# Micro.net
KiCad netlist of a schematic drawn in Altium Designer
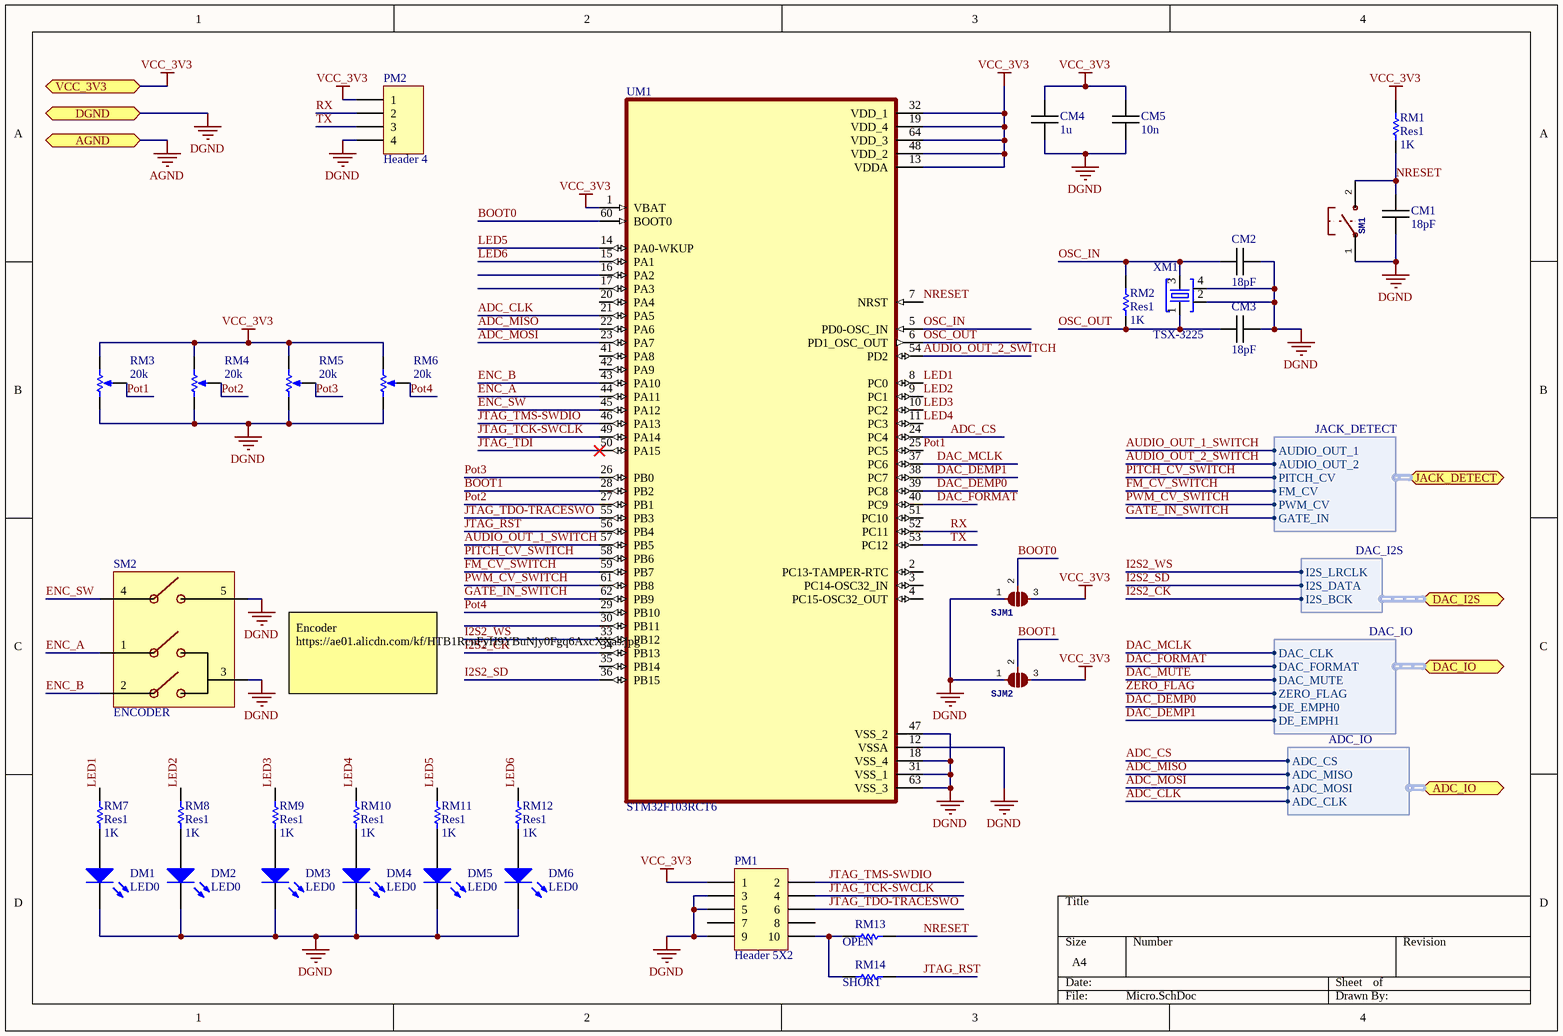
[diagram p0: Micro.SchDoc]

(export (version "E")
  (design (tool "Eeschema 10.0.6"))
  (components
    (comp (ref "CM1")
      (value "18pF")
      (footprint "C 0603 / 1608")
      (libsource (lib "Standard") (part "Capacitor"))
    )
    (comp (ref "CM2")
      (value "18pF")
      (footprint "C 0603 / 1608")
      (libsource (lib "Standard") (part "Capacitor"))
    )
    (comp (ref "CM3")
      (value "18pF")
      (footprint "C 0603 / 1608")
      (libsource (lib "Standard") (part "Capacitor"))
    )
    (comp (ref "CM4")
      (value "1u")
      (footprint "C 0603 / 1608")
      (libsource (lib "Standard") (part "Capacitor"))
    )
    (comp (ref "CM5")
      (value "10n")
      (footprint "C 0603 / 1608")
      (libsource (lib "Standard") (part "Capacitor"))
    )
    (comp (ref "DM1")
      (value "LED0")
      (footprint "LED2-2.54-D5.0MM")
      (description "Typical INFRARED GaAs LED")
      (fields (field (name "PUBLISHER") "Altium Limited"))
      (libsource (lib "Miscellaneous Devices") (part "LED0"))
    )
    (comp (ref "DM2")
      (value "LED0")
      (footprint "LED2-2.54-D5.0MM")
      (description "Typical INFRARED GaAs LED")
      (fields (field (name "PUBLISHER") "Altium Limited"))
      (libsource (lib "Miscellaneous Devices") (part "LED0"))
    )
    (comp (ref "DM3")
      (value "LED0")
      (footprint "LED2-2.54-D5.0MM")
      (description "Typical INFRARED GaAs LED")
      (fields (field (name "PUBLISHER") "Altium Limited"))
      (libsource (lib "Miscellaneous Devices") (part "LED0"))
    )
    (comp (ref "DM4")
      (value "LED0")
      (footprint "LED2-2.54-D5.0MM")
      (description "Typical INFRARED GaAs LED")
      (fields (field (name "PUBLISHER") "Altium Limited"))
      (libsource (lib "Miscellaneous Devices") (part "LED0"))
    )
    (comp (ref "DM5")
      (value "LED0")
      (footprint "LED2-2.54-D5.0MM")
      (description "Typical INFRARED GaAs LED")
      (fields (field (name "PUBLISHER") "Altium Limited"))
      (libsource (lib "Miscellaneous Devices") (part "LED0"))
    )
    (comp (ref "DM6")
      (value "LED0")
      (footprint "LED2-2.54-D5.0MM")
      (description "Typical INFRARED GaAs LED")
      (fields (field (name "PUBLISHER") "Altium Limited"))
      (libsource (lib "Miscellaneous Devices") (part "LED0"))
    )
    (comp (ref "PM1")
      (value "Header 5X2")
      (footprint "HDR2X5")
      (description "Header, 5-Pin, Dual row")
      (fields (field (name "PUBLISHER") "Altium Limited"))
      (libsource (lib "Miscellaneous Connectors") (part "Header 5X2"))
    )
    (comp (ref "PM2")
      (value "Header 4")
      (footprint "HDR1X4")
      (description "Header, 4-Pin")
      (fields (field (name "PUBLISHER") "Altium Limited"))
      (libsource (lib "Miscellaneous Connectors") (part "Header 4"))
    )
    (comp (ref "RM1")
      (value "Res1")
      (footprint "RES0603R")
      (description "Resistor")
      (fields (field (name "ALTIUM_VALUE") "1K") (field (name "PUBLISHER") "Altium Limited"))
      (libsource (lib "Standard") (part "Res1"))
    )
    (comp (ref "RM2")
      (value "Res1")
      (footprint "RES0603R")
      (description "Resistor")
      (fields (field (name "ALTIUM_VALUE") "1K") (field (name "PUBLISHER") "Altium Limited"))
      (libsource (lib "Standard") (part "Res1"))
    )
    (comp (ref "RM3")
      (value "20k")
      (footprint "POT-rv09")
      (description "Potentiometer")
      (fields (field (name "PUBLISHER") "Altium Limited"))
      (libsource (lib "Standard") (part "RPot"))
    )
    (comp (ref "RM4")
      (value "20k")
      (footprint "POT-rv09")
      (description "Potentiometer")
      (fields (field (name "PUBLISHER") "Altium Limited"))
      (libsource (lib "Standard") (part "RPot"))
    )
    (comp (ref "RM5")
      (value "20k")
      (footprint "POT-rv09")
      (description "Potentiometer")
      (fields (field (name "PUBLISHER") "Altium Limited"))
      (libsource (lib "Standard") (part "RPot"))
    )
    (comp (ref "RM6")
      (value "20k")
      (footprint "POT-rv09")
      (description "Potentiometer")
      (fields (field (name "PUBLISHER") "Altium Limited"))
      (libsource (lib "Standard") (part "RPot"))
    )
    (comp (ref "RM7")
      (value "Res1")
      (footprint "RES0603R")
      (description "Resistor")
      (fields (field (name "ALTIUM_VALUE") "1K") (field (name "PUBLISHER") "Altium Limited"))
      (libsource (lib "Standard") (part "Res1"))
    )
    (comp (ref "RM8")
      (value "Res1")
      (footprint "RES0603R")
      (description "Resistor")
      (fields (field (name "ALTIUM_VALUE") "1K") (field (name "PUBLISHER") "Altium Limited"))
      (libsource (lib "Standard") (part "Res1"))
    )
    (comp (ref "RM9")
      (value "Res1")
      (footprint "RES0603R")
      (description "Resistor")
      (fields (field (name "ALTIUM_VALUE") "1K") (field (name "PUBLISHER") "Altium Limited"))
      (libsource (lib "Standard") (part "Res1"))
    )
    (comp (ref "RM10")
      (value "Res1")
      (footprint "RES0603R")
      (description "Resistor")
      (fields (field (name "ALTIUM_VALUE") "1K") (field (name "PUBLISHER") "Altium Limited"))
      (libsource (lib "Standard") (part "Res1"))
    )
    (comp (ref "RM11")
      (value "Res1")
      (footprint "RES0603R")
      (description "Resistor")
      (fields (field (name "ALTIUM_VALUE") "1K") (field (name "PUBLISHER") "Altium Limited"))
      (libsource (lib "Standard") (part "Res1"))
    )
    (comp (ref "RM12")
      (value "Res1")
      (footprint "RES0603R")
      (description "Resistor")
      (fields (field (name "ALTIUM_VALUE") "1K") (field (name "PUBLISHER") "Altium Limited"))
      (libsource (lib "Standard") (part "Res1"))
    )
    (comp (ref "RM13")
      (value "OPEN")
      (footprint "RES0603R")
      (description "Resistor")
      (fields (field (name "Comment") "Res1") (field (name "PUBLISHER") "Altium Limited"))
      (libsource (lib "Standard") (part "Res1"))
    )
    (comp (ref "RM14")
      (value "SHORT")
      (footprint "RES0603R")
      (description "Resistor")
      (fields (field (name "Comment") "Res1") (field (name "PUBLISHER") "Altium Limited"))
      (libsource (lib "Standard") (part "Res1"))
    )
    (comp (ref "SJM1")
      (value "2-Way Solder Jumper")
      (footprint "SOLDERJUMPER_2WAY_OPEN_NOPASTE")
      (libsource (lib "Standard2") (part "SOLDERJUMPER_2WAY0603"))
    )
    (comp (ref "SJM2")
      (value "2-Way Solder Jumper")
      (footprint "SOLDERJUMPER_2WAY_OPEN_NOPASTE")
      (libsource (lib "Standard2") (part "SOLDERJUMPER_2WAY0603"))
    )
    (comp (ref "SM1")
      (value "Switch")
      (footprint "PUSH_SMD_3x4")
      (fields (field (name "MANUFACTURER") "Omron") (field (name "MPN") "B3U-1000P"))
      (libsource (lib "Switches") (part "B3U-1000P"))
    )
    (comp (ref "SM2")
      (value "ENCODER")
      (footprint "Rotary Encoder")
      (libsource (lib "Switches") (part "ENCODER"))
    )
    (comp (ref "UM1")
      (value "STM32F103RCT6")
      (footprint "QFP64P1200X1200X160-64N")
      (description "ARMÂ® CortexÂ®-M3 STM32F1 Microcontroller IC 32-Bit 72MHz 256KB _256K x 8_ FLASH")
      (fields (field (name "MF") "STMicroelectronics"))
      (libsource (lib "STM") (part "STM32F103RCT6"))
    )
    (comp (ref "XM1")
      (value "TSX-3225")
      (footprint "TSX-3225")
      (description "16MHz Â±10ppm Crystal 9pF 60 Ohms 4-SMD, No Lead")
      (fields (field (name "MF") "EPSON"))
      (libsource (lib "XTAL") (part "TSX-3225"))
    )
  )
  (nets
    (net (code "5") (name "/ADC_CLK") (class "Default")
      (node (ref "UM1") (pin "21") (pinfunction "PA5_21") (pintype "bidirectional"))
    )
    (net (code "6") (name "/ADC_CS") (class "Default")
      (node (ref "UM1") (pin "24") (pinfunction "PC4_24") (pintype "bidirectional"))
    )
    (net (code "7") (name "/ADC_MISO") (class "Default")
      (node (ref "UM1") (pin "22") (pinfunction "PA6_22") (pintype "bidirectional"))
    )
    (net (code "8") (name "/ADC_MOSI") (class "Default")
      (node (ref "UM1") (pin "23") (pinfunction "PA7_23") (pintype "bidirectional"))
    )
    (net (code "9") (name "/AUDIO_OUT_1_SWITCH") (class "Default")
      (node (ref "UM1") (pin "57") (pinfunction "PB5_57") (pintype "bidirectional"))
    )
    (net (code "10") (name "/AUDIO_OUT_2_SWITCH") (class "Default")
      (node (ref "UM1") (pin "54") (pinfunction "PD2_54") (pintype "bidirectional"))
    )
    (net (code "11") (name "/BOOT0") (class "Default")
      (node (ref "SJM1") (pin "2") (pinfunction "2_2") (pintype "passive"))
      (node (ref "UM1") (pin "60") (pinfunction "BOOT0_60") (pintype "input"))
    )
    (net (code "12") (name "/BOOT1") (class "Default")
      (node (ref "SJM2") (pin "2") (pinfunction "2_2") (pintype "passive"))
      (node (ref "UM1") (pin "28") (pinfunction "PB2_28") (pintype "bidirectional"))
    )
    (net (code "13") (name "/DAC_DEMP0") (class "Default")
      (node (ref "UM1") (pin "39") (pinfunction "PC8_39") (pintype "bidirectional"))
    )
    (net (code "14") (name "/DAC_DEMP1") (class "Default")
      (node (ref "UM1") (pin "38") (pinfunction "PC7_38") (pintype "bidirectional"))
    )
    (net (code "15") (name "/DAC_FORMAT") (class "Default")
      (node (ref "UM1") (pin "40") (pinfunction "PC9_40") (pintype "bidirectional"))
    )
    (net (code "16") (name "/DAC_MCLK") (class "Default")
      (node (ref "UM1") (pin "37") (pinfunction "PC6_37") (pintype "bidirectional"))
    )
    (net (code "18") (name "/ENC_A") (class "Default")
      (node (ref "SM2") (pin "1") (pinfunction "A_1") (pintype "passive"))
      (node (ref "UM1") (pin "44") (pinfunction "PA11_44") (pintype "bidirectional"))
    )
    (net (code "19") (name "/ENC_B") (class "Default")
      (node (ref "SM2") (pin "2") (pinfunction "B_2") (pintype "passive"))
      (node (ref "UM1") (pin "43") (pinfunction "PA10_43") (pintype "bidirectional"))
    )
    (net (code "20") (name "/ENC_SW") (class "Default")
      (node (ref "SM2") (pin "4") (pinfunction "SW_4") (pintype "passive"))
      (node (ref "UM1") (pin "45") (pinfunction "PA12_45") (pintype "bidirectional"))
    )
    (net (code "21") (name "/FM_CV_SWITCH") (class "Default")
      (node (ref "UM1") (pin "59") (pinfunction "PB7_59") (pintype "bidirectional"))
    )
    (net (code "22") (name "/GATE_IN_SWITCH") (class "Default")
      (node (ref "UM1") (pin "62") (pinfunction "PB9_62") (pintype "bidirectional"))
    )
    (net (code "23") (name "/I2S2_CK") (class "Default")
      (node (ref "UM1") (pin "34") (pinfunction "PB13_34") (pintype "bidirectional"))
    )
    (net (code "24") (name "/I2S2_SD") (class "Default")
      (node (ref "UM1") (pin "36") (pinfunction "PB15_36") (pintype "bidirectional"))
    )
    (net (code "25") (name "/I2S2_WS") (class "Default")
      (node (ref "UM1") (pin "33") (pinfunction "PB12_33") (pintype "bidirectional"))
    )
    (net (code "26") (name "/JTAG_RST") (class "Default")
      (node (ref "RM14") (pin "2") (pinfunction "2_2") (pintype "passive"))
      (node (ref "UM1") (pin "56") (pinfunction "PB4_56") (pintype "bidirectional"))
    )
    (net (code "27") (name "/JTAG_TCK-SWCLK") (class "Default")
      (node (ref "PM1") (pin "4") (pinfunction "4_4") (pintype "passive"))
      (node (ref "UM1") (pin "49") (pinfunction "PA14_49") (pintype "bidirectional"))
    )
    (net (code "28") (name "/JTAG_TDI") (class "Default")
      (node (ref "UM1") (pin "50") (pinfunction "PA15_50") (pintype "bidirectional+no_connect"))
    )
    (net (code "29") (name "/JTAG_TDO-TRACESWO") (class "Default")
      (node (ref "PM1") (pin "6") (pinfunction "6_6") (pintype "passive"))
      (node (ref "UM1") (pin "55") (pinfunction "PB3_55") (pintype "bidirectional"))
    )
    (net (code "30") (name "/JTAG_TMS-SWDIO") (class "Default")
      (node (ref "PM1") (pin "2") (pinfunction "2_2") (pintype "passive"))
      (node (ref "UM1") (pin "46") (pinfunction "PA13_46") (pintype "bidirectional"))
    )
    (net (code "31") (name "/LED1") (class "Default")
      (node (ref "RM7") (pin "1") (pinfunction "1_1") (pintype "passive"))
      (node (ref "UM1") (pin "8") (pinfunction "PC0_8") (pintype "bidirectional"))
    )
    (net (code "32") (name "/LED2") (class "Default")
      (node (ref "RM8") (pin "1") (pinfunction "1_1") (pintype "passive"))
      (node (ref "UM1") (pin "9") (pinfunction "PC1_9") (pintype "bidirectional"))
    )
    (net (code "33") (name "/LED3") (class "Default")
      (node (ref "RM9") (pin "1") (pinfunction "1_1") (pintype "passive"))
      (node (ref "UM1") (pin "10") (pinfunction "PC2_10") (pintype "bidirectional"))
    )
    (net (code "34") (name "/LED4") (class "Default")
      (node (ref "RM10") (pin "1") (pinfunction "1_1") (pintype "passive"))
      (node (ref "UM1") (pin "11") (pinfunction "PC3_11") (pintype "bidirectional"))
    )
    (net (code "35") (name "/LED5") (class "Default")
      (node (ref "RM11") (pin "1") (pinfunction "1_1") (pintype "passive"))
      (node (ref "UM1") (pin "14") (pinfunction "PA0-WKUP_14") (pintype "bidirectional"))
    )
    (net (code "36") (name "/LED6") (class "Default")
      (node (ref "RM12") (pin "1") (pinfunction "1_1") (pintype "passive"))
      (node (ref "UM1") (pin "15") (pinfunction "PA1_15") (pintype "bidirectional"))
    )
    (net (code "37") (name "/NRESET") (class "Default")
      (node (ref "CM1") (pin "2") (pinfunction "1_2") (pintype "passive"))
      (node (ref "RM1") (pin "2") (pinfunction "2_2") (pintype "passive"))
      (node (ref "RM13") (pin "2") (pinfunction "2_2") (pintype "passive"))
      (node (ref "SM1") (pin "2") (pinfunction "P$2_2") (pintype "passive"))
      (node (ref "UM1") (pin "7") (pinfunction "NRST_7") (pintype "input"))
    )
    (net (code "38") (name "/OSC_IN") (class "Default")
      (node (ref "CM2") (pin "2") (pinfunction "1_2") (pintype "passive"))
      (node (ref "RM2") (pin "1") (pinfunction "1_1") (pintype "passive"))
      (node (ref "UM1") (pin "5") (pinfunction "PD0-OSC_IN_5") (pintype "input"))
      (node (ref "XM1") (pin "3") (pinfunction "3_3") (pintype "passive"))
    )
    (net (code "39") (name "/OSC_OUT") (class "Default")
      (node (ref "CM3") (pin "2") (pinfunction "1_2") (pintype "passive"))
      (node (ref "RM2") (pin "2") (pinfunction "2_2") (pintype "passive"))
      (node (ref "UM1") (pin "6") (pinfunction "PD1_OSC_OUT_6") (pintype "output"))
      (node (ref "XM1") (pin "1") (pinfunction "1_1") (pintype "passive"))
    )
    (net (code "40") (name "/PITCH_CV_SWITCH") (class "Default")
      (node (ref "UM1") (pin "58") (pinfunction "PB6_58") (pintype "bidirectional"))
    )
    (net (code "41") (name "/PWM_CV_SWITCH") (class "Default")
      (node (ref "UM1") (pin "61") (pinfunction "PB8_61") (pintype "bidirectional"))
    )
    (net (code "42") (name "/Pot1") (class "Default")
      (node (ref "RM3") (pin "3") (pinfunction "TAP_3") (pintype "passive"))
      (node (ref "UM1") (pin "25") (pinfunction "PC5_25") (pintype "bidirectional"))
    )
    (net (code "43") (name "/Pot2") (class "Default")
      (node (ref "RM4") (pin "3") (pinfunction "TAP_3") (pintype "passive"))
      (node (ref "UM1") (pin "27") (pinfunction "PB1_27") (pintype "bidirectional"))
    )
    (net (code "44") (name "/Pot3") (class "Default")
      (node (ref "RM5") (pin "3") (pinfunction "TAP_3") (pintype "passive"))
      (node (ref "UM1") (pin "26") (pinfunction "PB0_26") (pintype "bidirectional"))
    )
    (net (code "45") (name "/Pot4") (class "Default")
      (node (ref "RM6") (pin "3") (pinfunction "TAP_3") (pintype "passive"))
      (node (ref "UM1") (pin "29") (pinfunction "PB10_29") (pintype "bidirectional"))
    )
    (net (code "46") (name "/RX") (class "Default")
      (node (ref "PM2") (pin "2") (pinfunction "2_2") (pintype "passive"))
      (node (ref "UM1") (pin "52") (pinfunction "PC11_52") (pintype "bidirectional"))
    )
    (net (code "47") (name "/TX") (class "Default")
      (node (ref "PM2") (pin "3") (pinfunction "3_3") (pintype "passive"))
      (node (ref "UM1") (pin "53") (pinfunction "PC12_53") (pintype "bidirectional"))
    )
    (net (code "54") (name "DGND") (class "Default")
      (node (ref "CM1") (pin "1") (pinfunction "1_1") (pintype "passive"))
      (node (ref "CM2") (pin "1") (pinfunction "1_1") (pintype "passive"))
      (node (ref "CM3") (pin "1") (pinfunction "1_1") (pintype "passive"))
      (node (ref "CM4") (pin "1") (pinfunction "1_1") (pintype "passive"))
      (node (ref "CM5") (pin "1") (pinfunction "1_1") (pintype "passive"))
      (node (ref "DM1") (pin "2") (pinfunction "K_2") (pintype "passive"))
      (node (ref "DM2") (pin "2") (pinfunction "K_2") (pintype "passive"))
      (node (ref "DM3") (pin "2") (pinfunction "K_2") (pintype "passive"))
      (node (ref "DM4") (pin "2") (pinfunction "K_2") (pintype "passive"))
      (node (ref "DM5") (pin "2") (pinfunction "K_2") (pintype "passive"))
      (node (ref "DM6") (pin "2") (pinfunction "K_2") (pintype "passive"))
      (node (ref "PM1") (pin "3") (pinfunction "3_3") (pintype "passive"))
      (node (ref "PM1") (pin "5") (pinfunction "5_5") (pintype "passive"))
      (node (ref "PM1") (pin "9") (pinfunction "9_9") (pintype "passive"))
      (node (ref "PM2") (pin "4") (pinfunction "4_4") (pintype "passive"))
      (node (ref "RM3") (pin "1") (pinfunction "TOP_1") (pintype "passive"))
      (node (ref "RM4") (pin "1") (pinfunction "TOP_1") (pintype "passive"))
      (node (ref "RM5") (pin "1") (pinfunction "TOP_1") (pintype "passive"))
      (node (ref "RM6") (pin "1") (pinfunction "TOP_1") (pintype "passive"))
      (node (ref "SJM1") (pin "1") (pinfunction "1_1") (pintype "passive"))
      (node (ref "SJM2") (pin "1") (pinfunction "1_1") (pintype "passive"))
      (node (ref "SM1") (pin "1") (pinfunction "P$1_1") (pintype "passive"))
      (node (ref "SM2") (pin "3") (pinfunction "ROT_COMMON_3") (pintype "passive"))
      (node (ref "SM2") (pin "5") (pinfunction "SW_GND_5") (pintype "passive"))
      (node (ref "UM1") (pin "12") (pinfunction "VSSA_12") (pintype "power_in"))
      (node (ref "UM1") (pin "18") (pinfunction "VSS_4_18") (pintype "power_in"))
      (node (ref "UM1") (pin "31") (pinfunction "VSS_1_31") (pintype "power_in"))
      (node (ref "UM1") (pin "47") (pinfunction "VSS_2_47") (pintype "power_in"))
      (node (ref "UM1") (pin "63") (pinfunction "VSS_3_63") (pintype "power_in"))
      (node (ref "XM1") (pin "2") (pinfunction "2_2") (pintype "passive"))
      (node (ref "XM1") (pin "4") (pinfunction "4_4") (pintype "passive"))
    )
    (net (code "55") (name "Net-(DM1-A)") (class "Default")
      (node (ref "DM1") (pin "1") (pinfunction "A_1") (pintype "passive"))
      (node (ref "RM7") (pin "2") (pinfunction "2_2") (pintype "passive"))
    )
    (net (code "56") (name "Net-(DM2-A)") (class "Default")
      (node (ref "DM2") (pin "1") (pinfunction "A_1") (pintype "passive"))
      (node (ref "RM8") (pin "2") (pinfunction "2_2") (pintype "passive"))
    )
    (net (code "57") (name "Net-(DM3-A)") (class "Default")
      (node (ref "DM3") (pin "1") (pinfunction "A_1") (pintype "passive"))
      (node (ref "RM9") (pin "2") (pinfunction "2_2") (pintype "passive"))
    )
    (net (code "58") (name "Net-(DM4-A)") (class "Default")
      (node (ref "DM4") (pin "1") (pinfunction "A_1") (pintype "passive"))
      (node (ref "RM10") (pin "2") (pinfunction "2_2") (pintype "passive"))
    )
    (net (code "59") (name "Net-(DM5-A)") (class "Default")
      (node (ref "DM5") (pin "1") (pinfunction "A_1") (pintype "passive"))
      (node (ref "RM11") (pin "2") (pinfunction "2_2") (pintype "passive"))
    )
    (net (code "60") (name "Net-(DM6-A)") (class "Default")
      (node (ref "DM6") (pin "1") (pinfunction "A_1") (pintype "passive"))
      (node (ref "RM12") (pin "2") (pinfunction "2_2") (pintype "passive"))
    )
    (net (code "61") (name "Net-(PM1-Pad10)") (class "Default")
      (node (ref "PM1") (pin "10") (pinfunction "10_10") (pintype "passive"))
      (node (ref "RM13") (pin "1") (pinfunction "1_1") (pintype "passive"))
      (node (ref "RM14") (pin "1") (pinfunction "1_1") (pintype "passive"))
    )
    (net (code "62") (name "VCC_3V3") (class "Default")
      (node (ref "CM4") (pin "2") (pinfunction "1_2") (pintype "passive"))
      (node (ref "CM5") (pin "2") (pinfunction "1_2") (pintype "passive"))
      (node (ref "PM1") (pin "1") (pinfunction "1_1") (pintype "passive"))
      (node (ref "PM2") (pin "1") (pinfunction "1_1") (pintype "passive"))
      (node (ref "RM1") (pin "1") (pinfunction "1_1") (pintype "passive"))
      (node (ref "RM3") (pin "2") (pinfunction "BOT_2") (pintype "passive"))
      (node (ref "RM4") (pin "2") (pinfunction "BOT_2") (pintype "passive"))
      (node (ref "RM5") (pin "2") (pinfunction "BOT_2") (pintype "passive"))
      (node (ref "RM6") (pin "2") (pinfunction "BOT_2") (pintype "passive"))
      (node (ref "SJM1") (pin "3") (pinfunction "3_3") (pintype "passive"))
      (node (ref "SJM2") (pin "3") (pinfunction "3_3") (pintype "passive"))
      (node (ref "UM1") (pin "1") (pinfunction "VBAT_1") (pintype "input"))
      (node (ref "UM1") (pin "13") (pinfunction "VDDA_13") (pintype "power_in"))
      (node (ref "UM1") (pin "19") (pinfunction "VDD_4_19") (pintype "power_in"))
      (node (ref "UM1") (pin "32") (pinfunction "VDD_1_32") (pintype "power_in"))
      (node (ref "UM1") (pin "48") (pinfunction "VDD_2_48") (pintype "power_in"))
      (node (ref "UM1") (pin "64") (pinfunction "VDD_3_64") (pintype "power_in"))
    )
    (net (code "63") (name "unconnected-(PM1-Pad7)") (class "Default")
      (node (ref "PM1") (pin "7") (pinfunction "7_7") (pintype "passive"))
    )
    (net (code "64") (name "unconnected-(PM1-Pad8)") (class "Default")
      (node (ref "PM1") (pin "8") (pinfunction "8_8") (pintype "passive"))
    )
    (net (code "65") (name "unconnected-(SM2-Pad1)") (class "Default")
      (node (ref "SM2") (pin "1") (pinfunction "1_1") (pintype "passive"))
    )
    (net (code "66") (name "unconnected-(SM2-Pad1)_1") (class "Default")
      (node (ref "SM2") (pin "1") (pinfunction "1_1") (pintype "passive"))
    )
    (net (code "67") (name "unconnected-(SM2-Pad1)_2") (class "Default")
      (node (ref "SM2") (pin "1") (pinfunction "1_1") (pintype "passive"))
    )
    (net (code "68") (name "unconnected-(SM2-Pad2)") (class "Default")
      (node (ref "SM2") (pin "2") (pinfunction "2_2") (pintype "passive"))
    )
    (net (code "69") (name "unconnected-(SM2-Pad2)_1") (class "Default")
      (node (ref "SM2") (pin "2") (pinfunction "2_2") (pintype "passive"))
    )
    (net (code "70") (name "unconnected-(SM2-Pad2)_2") (class "Default")
      (node (ref "SM2") (pin "2") (pinfunction "2_2") (pintype "passive"))
    )
    (net (code "71") (name "unconnected-(UM1-PA2-Pad16)") (class "Default")
      (node (ref "UM1") (pin "16") (pinfunction "PA2_16") (pintype "bidirectional"))
    )
    (net (code "72") (name "unconnected-(UM1-PA3-Pad17)") (class "Default")
      (node (ref "UM1") (pin "17") (pinfunction "PA3_17") (pintype "bidirectional"))
    )
    (net (code "73") (name "unconnected-(UM1-PA4-Pad20)") (class "Default")
      (node (ref "UM1") (pin "20") (pinfunction "PA4_20") (pintype "bidirectional"))
    )
    (net (code "74") (name "unconnected-(UM1-PA8-Pad41)") (class "Default")
      (node (ref "UM1") (pin "41") (pinfunction "PA8_41") (pintype "bidirectional"))
    )
    (net (code "75") (name "unconnected-(UM1-PA9-Pad42)") (class "Default")
      (node (ref "UM1") (pin "42") (pinfunction "PA9_42") (pintype "bidirectional"))
    )
    (net (code "76") (name "unconnected-(UM1-PB11-Pad30)") (class "Default")
      (node (ref "UM1") (pin "30") (pinfunction "PB11_30") (pintype "bidirectional"))
    )
    (net (code "77") (name "unconnected-(UM1-PB14-Pad35)") (class "Default")
      (node (ref "UM1") (pin "35") (pinfunction "PB14_35") (pintype "bidirectional"))
    )
    (net (code "78") (name "unconnected-(UM1-PC10-Pad51)") (class "Default")
      (node (ref "UM1") (pin "51") (pinfunction "PC10_51") (pintype "bidirectional"))
    )
    (net (code "79") (name "unconnected-(UM1-PC13-TAMPER-RTC-Pad2)") (class "Default")
      (node (ref "UM1") (pin "2") (pinfunction "PC13-TAMPER-RTC_2") (pintype "bidirectional"))
    )
    (net (code "80") (name "unconnected-(UM1-PC14-OSC32_IN-Pad3)") (class "Default")
      (node (ref "UM1") (pin "3") (pinfunction "PC14-OSC32_IN_3") (pintype "bidirectional"))
    )
    (net (code "81") (name "unconnected-(UM1-PC15-OSC32_OUT-Pad4)") (class "Default")
      (node (ref "UM1") (pin "4") (pinfunction "PC15-OSC32_OUT_4") (pintype "bidirectional"))
    )
  )
)
